# Soil_Temperature_Sensors.net
KiCad netlist of a schematic drawn in Altium Designer
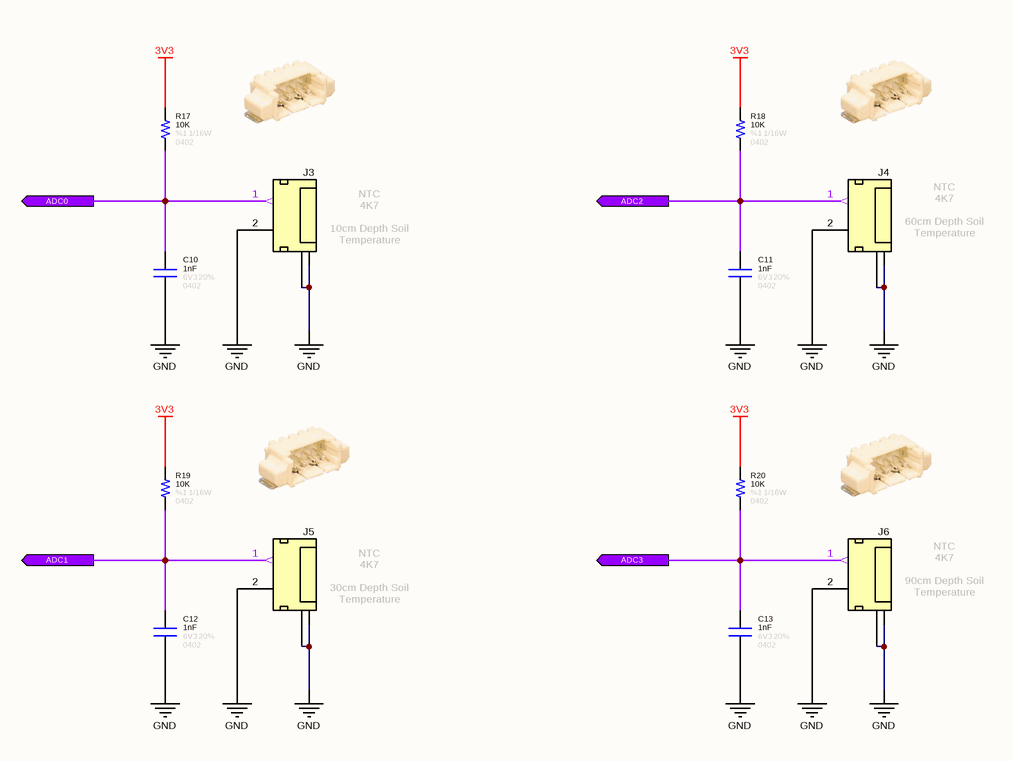
[diagram p0: Soil Temperature Sensors.SchDoc]

(export (version "E")
  (design (tool "Eeschema 10.0.6"))
  (components
    (comp (ref "C10")
      (value "1nF")
      (footprint "CAPACITOR_0402")
      (description "Capacitor - 1nF [0402] (Ceramic)")
      (fields
        (field (name "MANUFACTURER PART NUMBER") "04026C102MAT2A")
        (field (name "TOLERANCE") "20%")
        (field (name "CASE") "0402")
        (field (name "VOLTAGE") "6V3")
      )
      (libsource (lib "P101DA_Library") (part "Capacitor - 1nF [0402-6V3]"))
    )
    (comp (ref "C11")
      (value "1nF")
      (footprint "CAPACITOR_0402")
      (description "Capacitor - 1nF [0402] (Ceramic)")
      (fields
        (field (name "MANUFACTURER PART NUMBER") "04026C102MAT2A")
        (field (name "TOLERANCE") "20%")
        (field (name "CASE") "0402")
        (field (name "VOLTAGE") "6V3")
      )
      (libsource (lib "P101DA_Library") (part "Capacitor - 1nF [0402-6V3]"))
    )
    (comp (ref "C12")
      (value "1nF")
      (footprint "CAPACITOR_0402")
      (description "Capacitor - 1nF [0402] (Ceramic)")
      (fields
        (field (name "MANUFACTURER PART NUMBER") "04026C102MAT2A")
        (field (name "TOLERANCE") "20%")
        (field (name "CASE") "0402")
        (field (name "VOLTAGE") "6V3")
      )
      (libsource (lib "P101DA_Library") (part "Capacitor - 1nF [0402-6V3]"))
    )
    (comp (ref "C13")
      (value "1nF")
      (footprint "CAPACITOR_0402")
      (description "Capacitor - 1nF [0402] (Ceramic)")
      (fields
        (field (name "MANUFACTURER PART NUMBER") "04026C102MAT2A")
        (field (name "TOLERANCE") "20%")
        (field (name "CASE") "0402")
        (field (name "VOLTAGE") "6V3")
      )
      (libsource (lib "P101DA_Library") (part "Capacitor - 1nF [0402-6V3]"))
    )
    (comp (ref "J3")
      (value "2P SMD Tunic Connector")
      (footprint "Connector_Tunic 2P")
      (description "Mini Tunic Connector with 2P")
      (fields
        (field (name "MANUFACTURER PART NUMBER") "53261-0271")
        (field (name "MOUSER PART NUMBER") "538-53261-0271")
      )
      (libsource (lib "P101DA_Library") (part "Connector - Mini Tunic 2P (1.25)"))
    )
    (comp (ref "J4")
      (value "2P SMD Tunic Connector")
      (footprint "Connector_Tunic 2P")
      (description "Mini Tunic Connector with 2P")
      (fields
        (field (name "MANUFACTURER PART NUMBER") "53261-0271")
        (field (name "MOUSER PART NUMBER") "538-53261-0271")
      )
      (libsource (lib "P101DA_Library") (part "Connector - Mini Tunic 2P (1.25)"))
    )
    (comp (ref "J5")
      (value "2P SMD Tunic Connector")
      (footprint "Connector_Tunic 2P")
      (description "Mini Tunic Connector with 2P")
      (fields
        (field (name "MANUFACTURER PART NUMBER") "53261-0271")
        (field (name "MOUSER PART NUMBER") "538-53261-0271")
      )
      (libsource (lib "P101DA_Library") (part "Connector - Mini Tunic 2P (1.25)"))
    )
    (comp (ref "J6")
      (value "2P SMD Tunic Connector")
      (footprint "Connector_Tunic 2P")
      (description "Mini Tunic Connector with 2P")
      (fields
        (field (name "MANUFACTURER PART NUMBER") "53261-0271")
        (field (name "MOUSER PART NUMBER") "538-53261-0271")
      )
      (libsource (lib "P101DA_Library") (part "Connector - Mini Tunic 2P (1.25)"))
    )
    (comp (ref "R17")
      (value "10K")
      (footprint "RESISTOR_0402")
      (description "Thick Film Resistors - SMD 1/16 W 10 KOhm 1%")
      (fields
        (field (name "MANUFACTURER PART NUMBER") "CRCW040210K0FKED")
        (field (name "TOLERANCE") "%1")
        (field (name "CASE") "0402")
        (field (name "POWER") "1/16W")
        (field (name "Comment") "10K - 0402 - %1 - 1/16W")
      )
      (libsource (lib "P101DA_Library") (part "Resistor - 10K [0402]"))
    )
    (comp (ref "R18")
      (value "10K")
      (footprint "RESISTOR_0402")
      (description "Thick Film Resistors - SMD 1/16 W 10 KOhm 1%")
      (fields
        (field (name "MANUFACTURER PART NUMBER") "CRCW040210K0FKED")
        (field (name "TOLERANCE") "%1")
        (field (name "CASE") "0402")
        (field (name "POWER") "1/16W")
        (field (name "Comment") "10K - 0402 - %1 - 1/16W")
      )
      (libsource (lib "P101DA_Library") (part "Resistor - 10K [0402]"))
    )
    (comp (ref "R19")
      (value "10K")
      (footprint "RESISTOR_0402")
      (description "Thick Film Resistors - SMD 1/16 W 10 KOhm 1%")
      (fields
        (field (name "MANUFACTURER PART NUMBER") "CRCW040210K0FKED")
        (field (name "TOLERANCE") "%1")
        (field (name "CASE") "0402")
        (field (name "POWER") "1/16W")
        (field (name "Comment") "10K - 0402 - %1 - 1/16W")
      )
      (libsource (lib "P101DA_Library") (part "Resistor - 10K [0402]"))
    )
    (comp (ref "R20")
      (value "10K")
      (footprint "RESISTOR_0402")
      (description "Thick Film Resistors - SMD 1/16 W 10 KOhm 1%")
      (fields
        (field (name "MANUFACTURER PART NUMBER") "CRCW040210K0FKED")
        (field (name "TOLERANCE") "%1")
        (field (name "CASE") "0402")
        (field (name "POWER") "1/16W")
        (field (name "Comment") "10K - 0402 - %1 - 1/16W")
      )
      (libsource (lib "P101DA_Library") (part "Resistor - 10K [0402]"))
    )
  )
  (nets
    (net (code "1") (name "/ADC0") (class "Default")
      (node (ref "C10") (pin "2") (pinfunction "2_2") (pintype "passive"))
      (node (ref "J3") (pin "1") (pinfunction "Pin1_1") (pintype "output"))
      (node (ref "R17") (pin "1") (pinfunction "1_1") (pintype "passive"))
    )
    (net (code "2") (name "/ADC1") (class "Default")
      (node (ref "C12") (pin "2") (pinfunction "2_2") (pintype "passive"))
      (node (ref "J5") (pin "1") (pinfunction "Pin1_1") (pintype "output"))
      (node (ref "R19") (pin "1") (pinfunction "1_1") (pintype "passive"))
    )
    (net (code "3") (name "/ADC2") (class "Default")
      (node (ref "C11") (pin "2") (pinfunction "2_2") (pintype "passive"))
      (node (ref "J4") (pin "1") (pinfunction "Pin1_1") (pintype "output"))
      (node (ref "R18") (pin "1") (pinfunction "1_1") (pintype "passive"))
    )
    (net (code "4") (name "/ADC3") (class "Default")
      (node (ref "C13") (pin "2") (pinfunction "2_2") (pintype "passive"))
      (node (ref "J6") (pin "1") (pinfunction "Pin1_1") (pintype "output"))
      (node (ref "R20") (pin "1") (pinfunction "1_1") (pintype "passive"))
    )
    (net (code "5") (name "3V3") (class "Default")
      (node (ref "R17") (pin "2") (pinfunction "2_2") (pintype "passive"))
      (node (ref "R18") (pin "2") (pinfunction "2_2") (pintype "passive"))
      (node (ref "R19") (pin "2") (pinfunction "2_2") (pintype "passive"))
      (node (ref "R20") (pin "2") (pinfunction "2_2") (pintype "passive"))
    )
    (net (code "6") (name "GND") (class "Default")
      (node (ref "C10") (pin "1") (pinfunction "1_1") (pintype "passive"))
      (node (ref "C11") (pin "1") (pinfunction "1_1") (pintype "passive"))
      (node (ref "C12") (pin "1") (pinfunction "1_1") (pintype "passive"))
      (node (ref "C13") (pin "1") (pinfunction "1_1") (pintype "passive"))
      (node (ref "J3") (pin "2") (pinfunction "Pin2_2") (pintype "passive"))
      (node (ref "J3") (pin "3") (pinfunction "GND_3") (pintype "passive"))
      (node (ref "J3") (pin "4") (pinfunction "GND_4") (pintype "passive"))
      (node (ref "J4") (pin "2") (pinfunction "Pin2_2") (pintype "passive"))
      (node (ref "J4") (pin "3") (pinfunction "GND_3") (pintype "passive"))
      (node (ref "J4") (pin "4") (pinfunction "GND_4") (pintype "passive"))
      (node (ref "J5") (pin "2") (pinfunction "Pin2_2") (pintype "passive"))
      (node (ref "J5") (pin "3") (pinfunction "GND_3") (pintype "passive"))
      (node (ref "J5") (pin "4") (pinfunction "GND_4") (pintype "passive"))
      (node (ref "J6") (pin "2") (pinfunction "Pin2_2") (pintype "passive"))
      (node (ref "J6") (pin "3") (pinfunction "GND_3") (pintype "passive"))
      (node (ref "J6") (pin "4") (pinfunction "GND_4") (pintype "passive"))
    )
  )
)
